# cable-direct-adapter.net
KiCad netlist of a schematic drawn in EAGLE
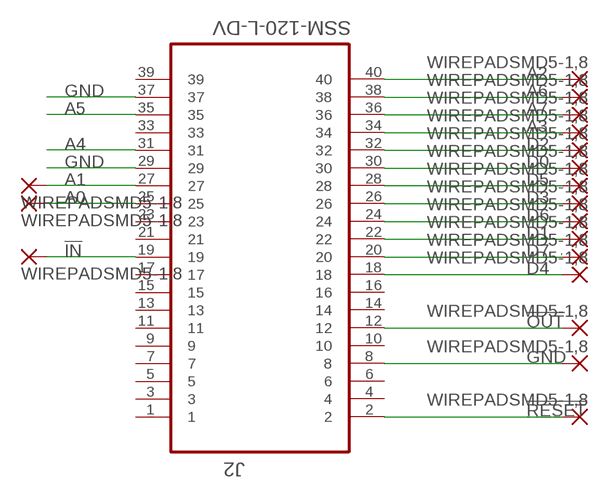
[diagram p0: schematic, sheet 1]

(export (version "E")
  (design (tool "Eeschema 10.0.6"))
  (components
    (comp (ref "J2")
      (value "SSM-120-L-DV")
      (footprint "eagle-import:SAMTEC_SSM-120-L-DV")
      (libsource (lib "eagle-import") (part "SSM-120-L-DV"))
    )
    (comp (ref "PAD1")
      (value "WIREPADSMD5-1,8")
      (footprint "eagle-import:5-1,8")
      (libsource (lib "eagle-import") (part "WIREPADSMD5-1,8"))
    )
    (comp (ref "PAD2")
      (value "WIREPADSMD5-1,8")
      (footprint "eagle-import:5-1,8")
      (libsource (lib "eagle-import") (part "WIREPADSMD5-1,8"))
    )
    (comp (ref "PAD3")
      (value "WIREPADSMD5-1,8")
      (footprint "eagle-import:5-1,8")
      (libsource (lib "eagle-import") (part "WIREPADSMD5-1,8"))
    )
    (comp (ref "PAD4")
      (value "WIREPADSMD5-1,8")
      (footprint "eagle-import:5-1,8")
      (libsource (lib "eagle-import") (part "WIREPADSMD5-1,8"))
    )
    (comp (ref "PAD5")
      (value "WIREPADSMD5-1,8")
      (footprint "eagle-import:5-1,8")
      (libsource (lib "eagle-import") (part "WIREPADSMD5-1,8"))
    )
    (comp (ref "PAD6")
      (value "WIREPADSMD5-1,8")
      (footprint "eagle-import:5-1,8")
      (libsource (lib "eagle-import") (part "WIREPADSMD5-1,8"))
    )
    (comp (ref "PAD7")
      (value "WIREPADSMD5-1,8")
      (footprint "eagle-import:5-1,8")
      (libsource (lib "eagle-import") (part "WIREPADSMD5-1,8"))
    )
    (comp (ref "PAD8")
      (value "WIREPADSMD5-1,8")
      (footprint "eagle-import:5-1,8")
      (libsource (lib "eagle-import") (part "WIREPADSMD5-1,8"))
    )
    (comp (ref "PAD9")
      (value "WIREPADSMD5-1,8")
      (footprint "eagle-import:5-1,8")
      (libsource (lib "eagle-import") (part "WIREPADSMD5-1,8"))
    )
    (comp (ref "PAD10")
      (value "WIREPADSMD5-1,8")
      (footprint "eagle-import:5-1,8")
      (libsource (lib "eagle-import") (part "WIREPADSMD5-1,8"))
    )
    (comp (ref "PAD11")
      (value "WIREPADSMD5-1,8")
      (footprint "eagle-import:5-1,8")
      (libsource (lib "eagle-import") (part "WIREPADSMD5-1,8"))
    )
    (comp (ref "PAD12")
      (value "WIREPADSMD5-1,8")
      (footprint "eagle-import:5-1,8")
      (libsource (lib "eagle-import") (part "WIREPADSMD5-1,8"))
    )
    (comp (ref "PAD13")
      (value "WIREPADSMD5-1,8")
      (footprint "eagle-import:5-1,8")
      (libsource (lib "eagle-import") (part "WIREPADSMD5-1,8"))
    )
    (comp (ref "PAD14")
      (value "WIREPADSMD5-1,8")
      (footprint "eagle-import:5-1,8")
      (libsource (lib "eagle-import") (part "WIREPADSMD5-1,8"))
    )
    (comp (ref "PAD15")
      (value "WIREPADSMD5-1,8")
      (footprint "eagle-import:5-1,8")
      (libsource (lib "eagle-import") (part "WIREPADSMD5-1,8"))
    )
    (comp (ref "PAD16")
      (value "WIREPADSMD5-1,8")
      (footprint "eagle-import:5-1,8")
      (libsource (lib "eagle-import") (part "WIREPADSMD5-1,8"))
    )
    (comp (ref "PAD17")
      (value "WIREPADSMD5-1,8")
      (footprint "eagle-import:5-1,8")
      (libsource (lib "eagle-import") (part "WIREPADSMD5-1,8"))
    )
    (comp (ref "PAD18")
      (value "WIREPADSMD5-1,8")
      (footprint "eagle-import:5-1,8")
      (libsource (lib "eagle-import") (part "WIREPADSMD5-1,8"))
    )
  )
  (nets
    (net (code "1") (name "/A0") (class "Default")
      (node (ref "J2") (pin "25") (pinfunction "25_25") (pintype "passive"))
      (node (ref "PAD17") (pin "1") (pinfunction "P_1") (pintype "passive"))
    )
    (net (code "2") (name "/A1") (class "Default")
      (node (ref "J2") (pin "27") (pinfunction "27_27") (pintype "passive"))
      (node (ref "PAD16") (pin "1") (pinfunction "P_1") (pintype "passive"))
    )
    (net (code "3") (name "/A2") (class "Default")
      (node (ref "J2") (pin "40") (pinfunction "40_40") (pintype "passive"))
      (node (ref "PAD1") (pin "1") (pinfunction "P_1") (pintype "passive"))
    )
    (net (code "4") (name "/A3") (class "Default")
      (node (ref "J2") (pin "34") (pinfunction "34_34") (pintype "passive"))
      (node (ref "PAD4") (pin "1") (pinfunction "P_1") (pintype "passive"))
    )
    (net (code "5") (name "/A4") (class "Default")
      (node (ref "J2") (pin "31") (pinfunction "31_31") (pintype "passive"))
    )
    (net (code "6") (name "/A5") (class "Default")
      (node (ref "J2") (pin "35") (pinfunction "35_35") (pintype "passive"))
    )
    (net (code "7") (name "/A6") (class "Default")
      (node (ref "J2") (pin "38") (pinfunction "38_38") (pintype "passive"))
      (node (ref "PAD2") (pin "1") (pinfunction "P_1") (pintype "passive"))
    )
    (net (code "8") (name "/A7") (class "Default")
      (node (ref "J2") (pin "36") (pinfunction "36_36") (pintype "passive"))
      (node (ref "PAD3") (pin "1") (pinfunction "P_1") (pintype "passive"))
    )
    (net (code "9") (name "/D0") (class "Default")
      (node (ref "J2") (pin "30") (pinfunction "30_30") (pintype "passive"))
      (node (ref "PAD6") (pin "1") (pinfunction "P_1") (pintype "passive"))
    )
    (net (code "10") (name "/D1") (class "Default")
      (node (ref "J2") (pin "22") (pinfunction "22_22") (pintype "passive"))
      (node (ref "PAD10") (pin "1") (pinfunction "P_1") (pintype "passive"))
    )
    (net (code "11") (name "/D2") (class "Default")
      (node (ref "J2") (pin "32") (pinfunction "32_32") (pintype "passive"))
      (node (ref "PAD5") (pin "1") (pinfunction "P_1") (pintype "passive"))
    )
    (net (code "12") (name "/D3") (class "Default")
      (node (ref "J2") (pin "26") (pinfunction "26_26") (pintype "passive"))
      (node (ref "PAD8") (pin "1") (pinfunction "P_1") (pintype "passive"))
    )
    (net (code "13") (name "/D4") (class "Default")
      (node (ref "J2") (pin "18") (pinfunction "18_18") (pintype "passive"))
      (node (ref "PAD12") (pin "1") (pinfunction "P_1") (pintype "passive"))
    )
    (net (code "14") (name "/D5") (class "Default")
      (node (ref "J2") (pin "28") (pinfunction "28_28") (pintype "passive"))
      (node (ref "PAD7") (pin "1") (pinfunction "P_1") (pintype "passive"))
    )
    (net (code "15") (name "/D6") (class "Default")
      (node (ref "J2") (pin "24") (pinfunction "24_24") (pintype "passive"))
      (node (ref "PAD9") (pin "1") (pinfunction "P_1") (pintype "passive"))
    )
    (net (code "16") (name "/D7") (class "Default")
      (node (ref "J2") (pin "20") (pinfunction "20_20") (pintype "passive"))
      (node (ref "PAD11") (pin "1") (pinfunction "P_1") (pintype "passive"))
    )
    (net (code "17") (name "/GND") (class "Default")
      (node (ref "J2") (pin "29") (pinfunction "29_29") (pintype "passive"))
      (node (ref "J2") (pin "37") (pinfunction "37_37") (pintype "passive"))
      (node (ref "J2") (pin "8") (pinfunction "8_8") (pintype "passive"))
      (node (ref "PAD14") (pin "1") (pinfunction "P_1") (pintype "passive"))
    )
    (net (code "18") (name "/~{IN}") (class "Default")
      (node (ref "J2") (pin "19") (pinfunction "19_19") (pintype "passive"))
      (node (ref "PAD18") (pin "1") (pinfunction "P_1") (pintype "passive"))
    )
    (net (code "19") (name "/~{OUT}") (class "Default")
      (node (ref "J2") (pin "12") (pinfunction "12_12") (pintype "passive"))
      (node (ref "PAD13") (pin "1") (pinfunction "P_1") (pintype "passive"))
    )
    (net (code "20") (name "/~{RESET}") (class "Default")
      (node (ref "J2") (pin "2") (pinfunction "2_2") (pintype "passive"))
      (node (ref "PAD15") (pin "1") (pinfunction "P_1") (pintype "passive"))
    )
    (net (code "21") (name "unconnected-(J2-Pad1)") (class "Default")
      (node (ref "J2") (pin "1") (pinfunction "1_1") (pintype "passive"))
    )
    (net (code "22") (name "unconnected-(J2-Pad3)") (class "Default")
      (node (ref "J2") (pin "3") (pinfunction "3_3") (pintype "passive"))
    )
    (net (code "23") (name "unconnected-(J2-Pad4)") (class "Default")
      (node (ref "J2") (pin "4") (pinfunction "4_4") (pintype "passive"))
    )
    (net (code "24") (name "unconnected-(J2-Pad5)") (class "Default")
      (node (ref "J2") (pin "5") (pinfunction "5_5") (pintype "passive"))
    )
    (net (code "25") (name "unconnected-(J2-Pad6)") (class "Default")
      (node (ref "J2") (pin "6") (pinfunction "6_6") (pintype "passive"))
    )
    (net (code "26") (name "unconnected-(J2-Pad7)") (class "Default")
      (node (ref "J2") (pin "7") (pinfunction "7_7") (pintype "passive"))
    )
    (net (code "27") (name "unconnected-(J2-Pad9)") (class "Default")
      (node (ref "J2") (pin "9") (pinfunction "9_9") (pintype "passive"))
    )
    (net (code "28") (name "unconnected-(J2-Pad10)") (class "Default")
      (node (ref "J2") (pin "10") (pinfunction "10_10") (pintype "passive"))
    )
    (net (code "29") (name "unconnected-(J2-Pad11)") (class "Default")
      (node (ref "J2") (pin "11") (pinfunction "11_11") (pintype "passive"))
    )
    (net (code "30") (name "unconnected-(J2-Pad13)") (class "Default")
      (node (ref "J2") (pin "13") (pinfunction "13_13") (pintype "passive"))
    )
    (net (code "31") (name "unconnected-(J2-Pad14)") (class "Default")
      (node (ref "J2") (pin "14") (pinfunction "14_14") (pintype "passive"))
    )
    (net (code "32") (name "unconnected-(J2-Pad15)") (class "Default")
      (node (ref "J2") (pin "15") (pinfunction "15_15") (pintype "passive"))
    )
    (net (code "33") (name "unconnected-(J2-Pad16)") (class "Default")
      (node (ref "J2") (pin "16") (pinfunction "16_16") (pintype "passive"))
    )
    (net (code "34") (name "unconnected-(J2-Pad17)") (class "Default")
      (node (ref "J2") (pin "17") (pinfunction "17_17") (pintype "passive"))
    )
    (net (code "35") (name "unconnected-(J2-Pad21)") (class "Default")
      (node (ref "J2") (pin "21") (pinfunction "21_21") (pintype "passive"))
    )
    (net (code "36") (name "unconnected-(J2-Pad23)") (class "Default")
      (node (ref "J2") (pin "23") (pinfunction "23_23") (pintype "passive"))
    )
    (net (code "37") (name "unconnected-(J2-Pad33)") (class "Default")
      (node (ref "J2") (pin "33") (pinfunction "33_33") (pintype "passive"))
    )
    (net (code "38") (name "unconnected-(J2-Pad39)") (class "Default")
      (node (ref "J2") (pin "39") (pinfunction "39_39") (pintype "passive"))
    )
  )
)
